# SN65HVD230.net
KiCad netlist of a schematic drawn in EAGLE
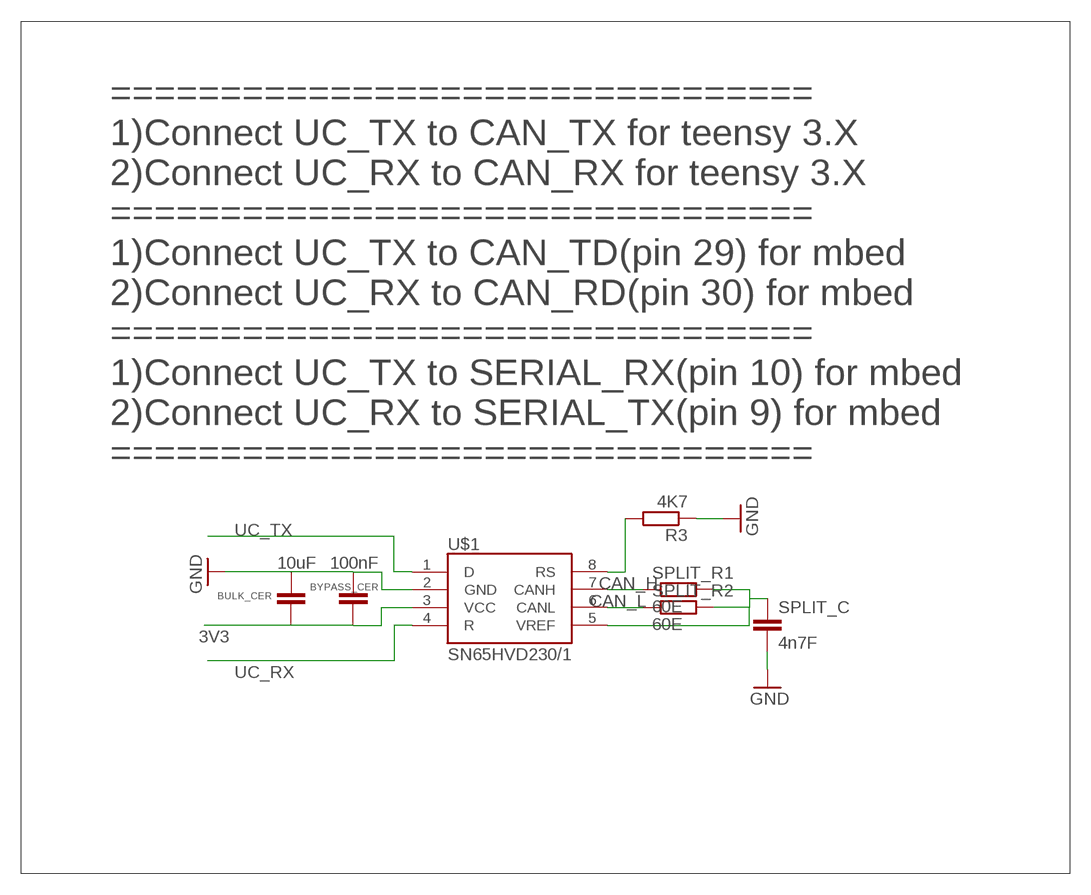
[diagram p0: schematic, sheet 1]

(export (version "E")
  (design (tool "Eeschema 10.0.6"))
  (components
    (comp (ref "BULK_CER")
      (value "10uF")
      (footprint "eagle-import:C0805")
      (libsource (lib "eagle-import") (part "C-EUC0805"))
    )
    (comp (ref "BYPASS_CER")
      (value "100nF")
      (footprint "eagle-import:C0805")
      (libsource (lib "eagle-import") (part "C-EUC0805"))
    )
    (comp (ref "R3")
      (value "4K7")
      (footprint "eagle-import:R0805")
      (libsource (lib "eagle-import") (part "R-EU_R0805"))
    )
    (comp (ref "SPLIT_C")
      (value "4n7F")
      (footprint "eagle-import:C0805")
      (libsource (lib "eagle-import") (part "C-EUC0805"))
    )
    (comp (ref "SPLIT_R1")
      (value "60E")
      (footprint "eagle-import:R0805")
      (libsource (lib "eagle-import") (part "R-EU_R0805"))
    )
    (comp (ref "SPLIT_R2")
      (value "60E")
      (footprint "eagle-import:R0805")
      (libsource (lib "eagle-import") (part "R-EU_R0805"))
    )
    (comp (ref "U$1")
      (value "SN65HVD230/1")
      (footprint "eagle-import:SO8")
      (libsource (lib "eagle-import") (part "SN65HVD230/1"))
    )
  )
  (nets
    (net (code "1") (name "/3V3") (class "Default")
      (node (ref "BULK_CER") (pin "1") (pinfunction "1_1") (pintype "passive"))
      (node (ref "BYPASS_CER") (pin "1") (pinfunction "1_1") (pintype "passive"))
      (node (ref "U$1") (pin "3") (pinfunction "VCC_3") (pintype "power_in"))
    )
    (net (code "2") (name "/CAN_H") (class "Default")
      (node (ref "SPLIT_R1") (pin "1") (pinfunction "1_1") (pintype "passive"))
      (node (ref "U$1") (pin "7") (pinfunction "CANH_7") (pintype "bidirectional"))
    )
    (net (code "3") (name "/CAN_L") (class "Default")
      (node (ref "SPLIT_R2") (pin "1") (pinfunction "1_1") (pintype "passive"))
      (node (ref "U$1") (pin "6") (pinfunction "CANL_6") (pintype "bidirectional"))
    )
    (net (code "4") (name "/UC_RX") (class "Default")
      (node (ref "U$1") (pin "4") (pinfunction "R_4") (pintype "bidirectional"))
    )
    (net (code "5") (name "/UC_TX") (class "Default")
      (node (ref "U$1") (pin "1") (pinfunction "D_1") (pintype "bidirectional"))
    )
    (net (code "6") (name "GND") (class "Default")
      (node (ref "BULK_CER") (pin "2") (pinfunction "2_2") (pintype "passive"))
      (node (ref "BYPASS_CER") (pin "2") (pinfunction "2_2") (pintype "passive"))
      (node (ref "R3") (pin "1") (pinfunction "1_1") (pintype "passive"))
      (node (ref "SPLIT_C") (pin "2") (pinfunction "2_2") (pintype "passive"))
      (node (ref "U$1") (pin "2") (pinfunction "GND_2") (pintype "power_in"))
    )
    (net (code "7") (name "Net-(U$1-RS)") (class "Default")
      (node (ref "R3") (pin "2") (pinfunction "2_2") (pintype "passive"))
      (node (ref "U$1") (pin "8") (pinfunction "RS_8") (pintype "bidirectional"))
    )
    (net (code "8") (name "Net-(U$1-VREF)") (class "Default")
      (node (ref "SPLIT_C") (pin "1") (pinfunction "1_1") (pintype "passive"))
      (node (ref "SPLIT_R1") (pin "2") (pinfunction "2_2") (pintype "passive"))
      (node (ref "SPLIT_R2") (pin "2") (pinfunction "2_2") (pintype "passive"))
      (node (ref "U$1") (pin "5") (pinfunction "VREF_5") (pintype "bidirectional"))
    )
  )
)
